# power_amp.net
KiCad netlist of a schematic drawn in Altium Designer
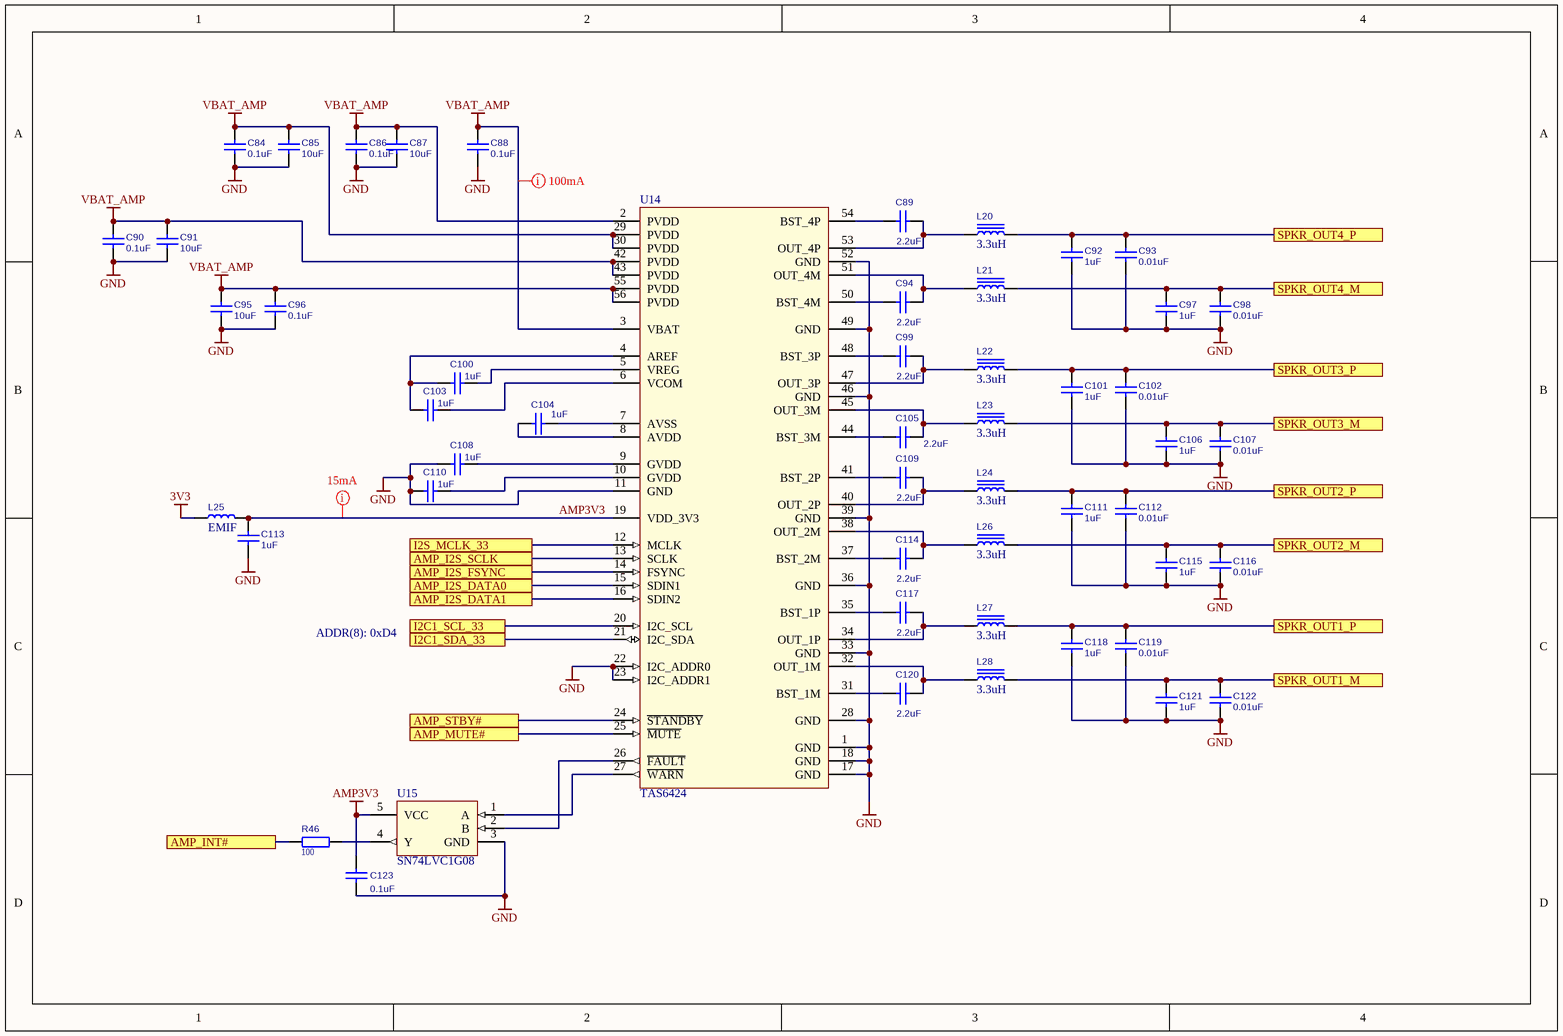
[diagram p0: power_amp.SchDoc]

(export (version "E")
  (design (tool "Eeschema 10.0.6"))
  (components
    (comp (ref "C84")
      (value "0.1uF")
      (footprint "Capacitors:C0603")
      (description "CAP_NPOL")
      (fields (field (name "Comment") "C1608X7R1H104K080AA"))
      (libsource (lib "capacitors") (part "CAP_NPOL"))
    )
    (comp (ref "C85")
      (value "10uF")
      (footprint "Capacitors:C0805")
      (description "CAP_NPOL")
      (fields (field (name "Comment") "GRM21BR61E106KA73L"))
      (libsource (lib "capacitors") (part "CAP_NPOL"))
    )
    (comp (ref "C86")
      (value "0.1uF")
      (footprint "Capacitors:C0603")
      (description "CAP_NPOL")
      (fields (field (name "Comment") "C1608X7R1H104K080AA"))
      (libsource (lib "capacitors") (part "CAP_NPOL"))
    )
    (comp (ref "C87")
      (value "10uF")
      (footprint "Capacitors:C0805")
      (description "CAP_NPOL")
      (fields (field (name "Comment") "GRM21BR61E106KA73L"))
      (libsource (lib "capacitors") (part "CAP_NPOL"))
    )
    (comp (ref "C88")
      (value "0.1uF")
      (footprint "Capacitors:C0603")
      (description "CAP_NPOL")
      (fields (field (name "Comment") "C1608X7R1H104K080AA"))
      (libsource (lib "capacitors") (part "CAP_NPOL"))
    )
    (comp (ref "C89")
      (value "2.2uF")
      (footprint "Capacitors:C0603")
      (description "CAP_NPOL")
      (fields (field (name "Comment") "GRM188R61H225KE11D"))
      (libsource (lib "capacitors") (part "CAP_NPOL"))
    )
    (comp (ref "C90")
      (value "0.1uF")
      (footprint "Capacitors:C0603")
      (description "CAP_NPOL")
      (fields (field (name "Comment") "C1608X7R1H104K080AA"))
      (libsource (lib "capacitors") (part "CAP_NPOL"))
    )
    (comp (ref "C91")
      (value "10uF")
      (footprint "Capacitors:C0805")
      (description "CAP_NPOL")
      (fields (field (name "Comment") "GRM21BR61E106KA73L"))
      (libsource (lib "capacitors") (part "CAP_NPOL"))
    )
    (comp (ref "C92")
      (value "1uF")
      (footprint "Capacitors:C0603")
      (description "CAP_NPOL")
      (fields (field (name "Comment") "CC0603KRX7R9BB105"))
      (libsource (lib "capacitors") (part "CAP_NPOL"))
    )
    (comp (ref "C93")
      (value "0.01uF")
      (footprint "Capacitors:C0603")
      (description "CAP_NPOL")
      (fields (field (name "Comment") "CL10B103KB8NNNC"))
      (libsource (lib "capacitors") (part "CAP_NPOL"))
    )
    (comp (ref "C94")
      (value "2.2uF")
      (footprint "Capacitors:C0603")
      (description "CAP_NPOL")
      (fields (field (name "Comment") "GRM188R61H225KE11D"))
      (libsource (lib "capacitors") (part "CAP_NPOL"))
    )
    (comp (ref "C95")
      (value "10uF")
      (footprint "Capacitors:C0805")
      (description "CAP_NPOL")
      (fields (field (name "Comment") "GRM21BR61E106KA73L"))
      (libsource (lib "capacitors") (part "CAP_NPOL"))
    )
    (comp (ref "C96")
      (value "0.1uF")
      (footprint "Capacitors:C0603")
      (description "CAP_NPOL")
      (fields (field (name "Comment") "C1608X7R1H104K080AA"))
      (libsource (lib "capacitors") (part "CAP_NPOL"))
    )
    (comp (ref "C97")
      (value "1uF")
      (footprint "Capacitors:C0603")
      (description "CAP_NPOL")
      (fields (field (name "Comment") "CC0603KRX7R9BB105"))
      (libsource (lib "capacitors") (part "CAP_NPOL"))
    )
    (comp (ref "C98")
      (value "0.01uF")
      (footprint "Capacitors:C0603")
      (description "CAP_NPOL")
      (fields (field (name "Comment") "CL10B103KB8NNNC"))
      (libsource (lib "capacitors") (part "CAP_NPOL"))
    )
    (comp (ref "C99")
      (value "2.2uF")
      (footprint "Capacitors:C0603")
      (description "CAP_NPOL")
      (fields (field (name "Comment") "GRM188R61H225KE11D"))
      (libsource (lib "capacitors") (part "CAP_NPOL"))
    )
    (comp (ref "C100")
      (value "1uF")
      (footprint "Capacitors:C0603")
      (description "CAP_NPOL")
      (fields (field (name "Comment") "CC0603KRX7R9BB105"))
      (libsource (lib "capacitors") (part "CAP_NPOL"))
    )
    (comp (ref "C101")
      (value "1uF")
      (footprint "Capacitors:C0603")
      (description "CAP_NPOL")
      (fields (field (name "Comment") "CC0603KRX7R9BB105"))
      (libsource (lib "capacitors") (part "CAP_NPOL"))
    )
    (comp (ref "C102")
      (value "0.01uF")
      (footprint "Capacitors:C0603")
      (description "CAP_NPOL")
      (fields (field (name "Comment") "CL10B103KB8NNNC"))
      (libsource (lib "capacitors") (part "CAP_NPOL"))
    )
    (comp (ref "C103")
      (value "1uF")
      (footprint "Capacitors:C0603")
      (description "CAP_NPOL")
      (fields (field (name "Comment") "CC0603KRX7R9BB105"))
      (libsource (lib "capacitors") (part "CAP_NPOL"))
    )
    (comp (ref "C104")
      (value "1uF")
      (footprint "Capacitors:C0603")
      (description "CAP_NPOL")
      (fields (field (name "Comment") "CC0603KRX7R9BB105"))
      (libsource (lib "capacitors") (part "CAP_NPOL"))
    )
    (comp (ref "C105")
      (value "2.2uF")
      (footprint "Capacitors:C0603")
      (description "CAP_NPOL")
      (fields (field (name "Comment") "GRM188R61H225KE11D"))
      (libsource (lib "capacitors") (part "CAP_NPOL"))
    )
    (comp (ref "C106")
      (value "1uF")
      (footprint "Capacitors:C0603")
      (description "CAP_NPOL")
      (fields (field (name "Comment") "CC0603KRX7R9BB105"))
      (libsource (lib "capacitors") (part "CAP_NPOL"))
    )
    (comp (ref "C107")
      (value "0.01uF")
      (footprint "Capacitors:C0603")
      (description "CAP_NPOL")
      (fields (field (name "Comment") "CL10B103KB8NNNC"))
      (libsource (lib "capacitors") (part "CAP_NPOL"))
    )
    (comp (ref "C108")
      (value "1uF")
      (footprint "Capacitors:C0603")
      (description "CAP_NPOL")
      (fields (field (name "Comment") "CC0603KRX7R9BB105"))
      (libsource (lib "capacitors") (part "CAP_NPOL"))
    )
    (comp (ref "C109")
      (value "2.2uF")
      (footprint "Capacitors:C0603")
      (description "CAP_NPOL")
      (fields (field (name "Comment") "GRM188R61H225KE11D"))
      (libsource (lib "capacitors") (part "CAP_NPOL"))
    )
    (comp (ref "C110")
      (value "1uF")
      (footprint "Capacitors:C0603")
      (description "CAP_NPOL")
      (fields (field (name "Comment") "CC0603KRX7R9BB105"))
      (libsource (lib "capacitors") (part "CAP_NPOL"))
    )
    (comp (ref "C111")
      (value "1uF")
      (footprint "Capacitors:C0603")
      (description "CAP_NPOL")
      (fields (field (name "Comment") "CC0603KRX7R9BB105"))
      (libsource (lib "capacitors") (part "CAP_NPOL"))
    )
    (comp (ref "C112")
      (value "0.01uF")
      (footprint "Capacitors:C0603")
      (description "CAP_NPOL")
      (fields (field (name "Comment") "CL10B103KB8NNNC"))
      (libsource (lib "capacitors") (part "CAP_NPOL"))
    )
    (comp (ref "C113")
      (value "1uF")
      (footprint "Capacitors:C0603")
      (description "CAP_NPOL")
      (fields (field (name "Comment") "CC0603KRX7R9BB105"))
      (libsource (lib "capacitors") (part "CAP_NPOL"))
    )
    (comp (ref "C114")
      (value "2.2uF")
      (footprint "Capacitors:C0603")
      (description "CAP_NPOL")
      (fields (field (name "Comment") "GRM188R61H225KE11D"))
      (libsource (lib "capacitors") (part "CAP_NPOL"))
    )
    (comp (ref "C115")
      (value "1uF")
      (footprint "Capacitors:C0603")
      (description "CAP_NPOL")
      (fields (field (name "Comment") "CC0603KRX7R9BB105"))
      (libsource (lib "capacitors") (part "CAP_NPOL"))
    )
    (comp (ref "C116")
      (value "0.01uF")
      (footprint "Capacitors:C0603")
      (description "CAP_NPOL")
      (fields (field (name "Comment") "CL10B103KB8NNNC"))
      (libsource (lib "capacitors") (part "CAP_NPOL"))
    )
    (comp (ref "C117")
      (value "2.2uF")
      (footprint "Capacitors:C0603")
      (description "CAP_NPOL")
      (fields (field (name "Comment") "GRM188R61H225KE11D"))
      (libsource (lib "capacitors") (part "CAP_NPOL"))
    )
    (comp (ref "C118")
      (value "1uF")
      (footprint "Capacitors:C0603")
      (description "CAP_NPOL")
      (fields (field (name "Comment") "CC0603KRX7R9BB105"))
      (libsource (lib "capacitors") (part "CAP_NPOL"))
    )
    (comp (ref "C119")
      (value "0.01uF")
      (footprint "Capacitors:C0603")
      (description "CAP_NPOL")
      (fields (field (name "Comment") "CL10B103KB8NNNC"))
      (libsource (lib "capacitors") (part "CAP_NPOL"))
    )
    (comp (ref "C120")
      (value "2.2uF")
      (footprint "Capacitors:C0603")
      (description "CAP_NPOL")
      (fields (field (name "Comment") "GRM188R61H225KE11D"))
      (libsource (lib "capacitors") (part "CAP_NPOL"))
    )
    (comp (ref "C121")
      (value "1uF")
      (footprint "Capacitors:C0603")
      (description "CAP_NPOL")
      (fields (field (name "Comment") "CC0603KRX7R9BB105"))
      (libsource (lib "capacitors") (part "CAP_NPOL"))
    )
    (comp (ref "C122")
      (value "0.01uF")
      (footprint "Capacitors:C0603")
      (description "CAP_NPOL")
      (fields (field (name "Comment") "CL10B103KB8NNNC"))
      (libsource (lib "capacitors") (part "CAP_NPOL"))
    )
    (comp (ref "C123")
      (value "0.1uF")
      (footprint "Capacitors:C0603")
      (description "CAP_NPOL")
      (fields (field (name "Comment") "CC0603KRX7R9BB104"))
      (libsource (lib "capacitors") (part "CAP_NPOL"))
    )
    (comp (ref "L20")
      (value "3.3uH")
      (footprint "IHLP-2525CZ")
      (description "IND_W_IRON")
      (fields (field (name "Comment") "IHLP2525CZER3R3M01"))
      (libsource (lib "inductors") (part "IND_W_IRON"))
    )
    (comp (ref "L21")
      (value "3.3uH")
      (footprint "IHLP-2525CZ")
      (description "IND_W_IRON")
      (fields (field (name "Comment") "IHLP2525CZER3R3M01"))
      (libsource (lib "inductors") (part "IND_W_IRON"))
    )
    (comp (ref "L22")
      (value "3.3uH")
      (footprint "IHLP-2525CZ")
      (description "IND_W_IRON")
      (fields (field (name "Comment") "IHLP2525CZER3R3M01"))
      (libsource (lib "inductors") (part "IND_W_IRON"))
    )
    (comp (ref "L23")
      (value "3.3uH")
      (footprint "IHLP-2525CZ")
      (description "IND_W_IRON")
      (fields (field (name "Comment") "IHLP2525CZER3R3M01"))
      (libsource (lib "inductors") (part "IND_W_IRON"))
    )
    (comp (ref "L24")
      (value "3.3uH")
      (footprint "IHLP-2525CZ")
      (description "IND_W_IRON")
      (fields (field (name "Comment") "IHLP2525CZER3R3M01"))
      (libsource (lib "inductors") (part "IND_W_IRON"))
    )
    (comp (ref "L25")
      (value "EMIF")
      (footprint "IND0805")
      (description "IND_WO_IRON")
      (fields (field (name "Comment") "BLM21PG221SN1D"))
      (libsource (lib "inductors") (part "IND_WO_IRON"))
    )
    (comp (ref "L26")
      (value "3.3uH")
      (footprint "IHLP-2525CZ")
      (description "IND_W_IRON")
      (fields (field (name "Comment") "IHLP2525CZER3R3M01"))
      (libsource (lib "inductors") (part "IND_W_IRON"))
    )
    (comp (ref "L27")
      (value "3.3uH")
      (footprint "IHLP-2525CZ")
      (description "IND_W_IRON")
      (fields (field (name "Comment") "IHLP2525CZER3R3M01"))
      (libsource (lib "inductors") (part "IND_W_IRON"))
    )
    (comp (ref "L28")
      (value "3.3uH")
      (footprint "IHLP-2525CZ")
      (description "IND_W_IRON")
      (fields (field (name "Comment") "IHLP2525CZER3R3M01"))
      (libsource (lib "inductors") (part "IND_W_IRON"))
    )
    (comp (ref "R46")
      (value "100")
      (footprint "R0603")
      (description "RES")
      (libsource (lib "resistors") (part "RESISTOR"))
    )
    (comp (ref "U14") (value "TAS6424") (footprint "HSSOP-56") (libsource (lib "TAS6424") (part "TAS6424")))
    (comp (ref "U15")
      (value "SN74LVC1G08")
      (footprint "SOT-23-5")
      (fields (field (name "Comment") "SN74LVC1G08DBVR"))
      (libsource (lib "SN74LVC1G08") (part "SN74LVC1G08"))
    )
  )
  (nets
    (net (code "1") (name "/AMP_I2S_DATA0") (class "Default")
      (node (ref "U14") (pin "15") (pinfunction "SDIN1_15") (pintype "input"))
    )
    (net (code "2") (name "/AMP_I2S_DATA1") (class "Default")
      (node (ref "U14") (pin "16") (pinfunction "SDIN2_16") (pintype "input"))
    )
    (net (code "3") (name "/AMP_I2S_FSYNC") (class "Default")
      (node (ref "U14") (pin "14") (pinfunction "FSYNC_14") (pintype "input"))
    )
    (net (code "4") (name "/AMP_I2S_SCLK") (class "Default")
      (node (ref "U14") (pin "13") (pinfunction "SCLK_13") (pintype "input"))
    )
    (net (code "5") (name "/AMP_INT#") (class "Default")
      (node (ref "R46") (pin "1") (pinfunction "1_1") (pintype "passive"))
    )
    (net (code "6") (name "/AMP_MUTE#") (class "Default")
      (node (ref "U14") (pin "25") (pinfunction "~{MUTE}_25") (pintype "input"))
    )
    (net (code "7") (name "/AMP_STBY#") (class "Default")
      (node (ref "U14") (pin "24") (pinfunction "~{STANDBY}_24") (pintype "input"))
    )
    (net (code "8") (name "/I2C1_SCL_33") (class "Default")
      (node (ref "U14") (pin "20") (pinfunction "I2C_SCL_20") (pintype "input"))
    )
    (net (code "9") (name "/I2C1_SDA_33") (class "Default")
      (node (ref "U14") (pin "21") (pinfunction "I2C_SDA_21") (pintype "bidirectional"))
    )
    (net (code "10") (name "/I2S_MCLK_33") (class "Default")
      (node (ref "U14") (pin "12") (pinfunction "MCLK_12") (pintype "input"))
    )
    (net (code "11") (name "/SPKR_OUT1_M") (class "Default")
      (node (ref "C121") (pin "1") (pinfunction "1_1") (pintype "passive"))
      (node (ref "C122") (pin "1") (pinfunction "1_1") (pintype "passive"))
      (node (ref "L28") (pin "2") (pintype "passive"))
    )
    (net (code "12") (name "/SPKR_OUT1_P") (class "Default")
      (node (ref "C118") (pin "1") (pinfunction "1_1") (pintype "passive"))
      (node (ref "C119") (pin "1") (pinfunction "1_1") (pintype "passive"))
      (node (ref "L27") (pin "2") (pintype "passive"))
    )
    (net (code "13") (name "/SPKR_OUT2_M") (class "Default")
      (node (ref "C115") (pin "1") (pinfunction "1_1") (pintype "passive"))
      (node (ref "C116") (pin "1") (pinfunction "1_1") (pintype "passive"))
      (node (ref "L26") (pin "2") (pintype "passive"))
    )
    (net (code "14") (name "/SPKR_OUT2_P") (class "Default")
      (node (ref "C111") (pin "1") (pinfunction "1_1") (pintype "passive"))
      (node (ref "C112") (pin "1") (pinfunction "1_1") (pintype "passive"))
      (node (ref "L24") (pin "2") (pintype "passive"))
    )
    (net (code "15") (name "/SPKR_OUT3_M") (class "Default")
      (node (ref "C106") (pin "1") (pinfunction "1_1") (pintype "passive"))
      (node (ref "C107") (pin "1") (pinfunction "1_1") (pintype "passive"))
      (node (ref "L23") (pin "2") (pintype "passive"))
    )
    (net (code "16") (name "/SPKR_OUT3_P") (class "Default")
      (node (ref "C101") (pin "1") (pinfunction "1_1") (pintype "passive"))
      (node (ref "C102") (pin "1") (pinfunction "1_1") (pintype "passive"))
      (node (ref "L22") (pin "2") (pintype "passive"))
    )
    (net (code "17") (name "/SPKR_OUT4_M") (class "Default")
      (node (ref "C97") (pin "1") (pinfunction "1_1") (pintype "passive"))
      (node (ref "C98") (pin "1") (pinfunction "1_1") (pintype "passive"))
      (node (ref "L21") (pin "2") (pintype "passive"))
    )
    (net (code "18") (name "/SPKR_OUT4_P") (class "Default")
      (node (ref "C92") (pin "1") (pinfunction "1_1") (pintype "passive"))
      (node (ref "C93") (pin "1") (pinfunction "1_1") (pintype "passive"))
      (node (ref "L20") (pin "2") (pintype "passive"))
    )
    (net (code "19") (name "3V3") (class "Default") (node (ref "L25") (pin "2") (pintype "passive")))
    (net (code "20") (name "AMP3V3") (class "Default")
      (node (ref "C113") (pin "1") (pinfunction "1_1") (pintype "passive"))
      (node (ref "C123") (pin "1") (pinfunction "1_1") (pintype "passive"))
      (node (ref "L25") (pin "1") (pintype "passive"))
      (node (ref "U14") (pin "19") (pinfunction "VDD_3V3_19") (pintype "power_in"))
      (node (ref "U15") (pin "5") (pinfunction "VCC_5") (pintype "power_in"))
    )
    (net (code "21") (name "GND") (class "Default")
      (node (ref "C101") (pin "2") (pinfunction "2_2") (pintype "passive"))
      (node (ref "C102") (pin "2") (pinfunction "2_2") (pintype "passive"))
      (node (ref "C106") (pin "2") (pinfunction "2_2") (pintype "passive"))
      (node (ref "C107") (pin "2") (pinfunction "2_2") (pintype "passive"))
      (node (ref "C108") (pin "1") (pinfunction "1_1") (pintype "passive"))
      (node (ref "C110") (pin "1") (pinfunction "1_1") (pintype "passive"))
      (node (ref "C111") (pin "2") (pinfunction "2_2") (pintype "passive"))
      (node (ref "C112") (pin "2") (pinfunction "2_2") (pintype "passive"))
      (node (ref "C113") (pin "2") (pinfunction "2_2") (pintype "passive"))
      (node (ref "C115") (pin "2") (pinfunction "2_2") (pintype "passive"))
      (node (ref "C116") (pin "2") (pinfunction "2_2") (pintype "passive"))
      (node (ref "C118") (pin "2") (pinfunction "2_2") (pintype "passive"))
      (node (ref "C119") (pin "2") (pinfunction "2_2") (pintype "passive"))
      (node (ref "C121") (pin "2") (pinfunction "2_2") (pintype "passive"))
      (node (ref "C122") (pin "2") (pinfunction "2_2") (pintype "passive"))
      (node (ref "C123") (pin "2") (pinfunction "2_2") (pintype "passive"))
      (node (ref "C84") (pin "2") (pinfunction "2_2") (pintype "passive"))
      (node (ref "C85") (pin "2") (pinfunction "2_2") (pintype "passive"))
      (node (ref "C86") (pin "2") (pinfunction "2_2") (pintype "passive"))
      (node (ref "C87") (pin "2") (pinfunction "2_2") (pintype "passive"))
      (node (ref "C88") (pin "2") (pinfunction "2_2") (pintype "passive"))
      (node (ref "C90") (pin "2") (pinfunction "2_2") (pintype "passive"))
      (node (ref "C91") (pin "2") (pinfunction "2_2") (pintype "passive"))
      (node (ref "C92") (pin "2") (pinfunction "2_2") (pintype "passive"))
      (node (ref "C93") (pin "2") (pinfunction "2_2") (pintype "passive"))
      (node (ref "C95") (pin "2") (pinfunction "2_2") (pintype "passive"))
      (node (ref "C96") (pin "2") (pinfunction "2_2") (pintype "passive"))
      (node (ref "C97") (pin "2") (pinfunction "2_2") (pintype "passive"))
      (node (ref "C98") (pin "2") (pinfunction "2_2") (pintype "passive"))
      (node (ref "U14") (pin "1") (pinfunction "GND_1") (pintype "power_in"))
      (node (ref "U14") (pin "11") (pinfunction "GND_11") (pintype "power_in"))
      (node (ref "U14") (pin "17") (pinfunction "GND_17") (pintype "power_in"))
      (node (ref "U14") (pin "18") (pinfunction "GND_18") (pintype "power_in"))
      (node (ref "U14") (pin "22") (pinfunction "I2C_ADDR0_22") (pintype "input"))
      (node (ref "U14") (pin "23") (pinfunction "I2C_ADDR1_23") (pintype "input"))
      (node (ref "U14") (pin "28") (pinfunction "GND_28") (pintype "power_in"))
      (node (ref "U14") (pin "33") (pinfunction "GND_33") (pintype "power_in"))
      (node (ref "U14") (pin "36") (pinfunction "GND_36") (pintype "power_in"))
      (node (ref "U14") (pin "39") (pinfunction "GND_39") (pintype "power_in"))
      (node (ref "U14") (pin "46") (pinfunction "GND_46") (pintype "power_in"))
      (node (ref "U14") (pin "49") (pinfunction "GND_49") (pintype "power_in"))
      (node (ref "U14") (pin "52") (pinfunction "GND_52") (pintype "power_in"))
      (node (ref "U15") (pin "3") (pinfunction "GND_3") (pintype "power_in"))
    )
    (net (code "22") (name "Net-(C108-Pad2)") (class "Default")
      (node (ref "C108") (pin "2") (pinfunction "2_2") (pintype "passive"))
      (node (ref "U14") (pin "9") (pinfunction "GVDD_9") (pintype "power_in"))
    )
    (net (code "23") (name "Net-(C110-Pad2)") (class "Default")
      (node (ref "C110") (pin "2") (pinfunction "2_2") (pintype "passive"))
      (node (ref "U14") (pin "10") (pinfunction "GVDD_10") (pintype "power_in"))
    )
    (net (code "24") (name "Net-(U14-AREF)") (class "Default")
      (node (ref "C100") (pin "1") (pinfunction "1_1") (pintype "passive"))
      (node (ref "C103") (pin "1") (pinfunction "1_1") (pintype "passive"))
      (node (ref "U14") (pin "4") (pinfunction "AREF_4") (pintype "power_in"))
    )
    (net (code "25") (name "Net-(U14-AVDD)") (class "Default")
      (node (ref "C104") (pin "1") (pinfunction "1_1") (pintype "passive"))
      (node (ref "U14") (pin "8") (pinfunction "AVDD_8") (pintype "power_in"))
    )
    (net (code "26") (name "Net-(U14-AVSS)") (class "Default")
      (node (ref "C104") (pin "2") (pinfunction "2_2") (pintype "passive"))
      (node (ref "U14") (pin "7") (pinfunction "AVSS_7") (pintype "power_in"))
    )
    (net (code "27") (name "Net-(U14-BST_1M)") (class "Default")
      (node (ref "C120") (pin "2") (pinfunction "2_2") (pintype "passive"))
      (node (ref "U14") (pin "31") (pinfunction "BST_1M_31") (pintype "power_in"))
    )
    (net (code "28") (name "Net-(U14-BST_1P)") (class "Default")
      (node (ref "C117") (pin "2") (pinfunction "2_2") (pintype "passive"))
      (node (ref "U14") (pin "35") (pinfunction "BST_1P_35") (pintype "power_in"))
    )
    (net (code "29") (name "Net-(U14-BST_2M)") (class "Default")
      (node (ref "C114") (pin "2") (pinfunction "2_2") (pintype "passive"))
      (node (ref "U14") (pin "37") (pinfunction "BST_2M_37") (pintype "power_in"))
    )
    (net (code "30") (name "Net-(U14-BST_2P)") (class "Default")
      (node (ref "C109") (pin "2") (pinfunction "2_2") (pintype "passive"))
      (node (ref "U14") (pin "41") (pinfunction "BST_2P_41") (pintype "power_in"))
    )
    (net (code "31") (name "Net-(U14-BST_3M)") (class "Default")
      (node (ref "C105") (pin "2") (pinfunction "2_2") (pintype "passive"))
      (node (ref "U14") (pin "44") (pinfunction "BST_3M_44") (pintype "power_in"))
    )
    (net (code "32") (name "Net-(U14-BST_3P)") (class "Default")
      (node (ref "C99") (pin "2") (pinfunction "2_2") (pintype "passive"))
      (node (ref "U14") (pin "48") (pinfunction "BST_3P_48") (pintype "power_in"))
    )
    (net (code "33") (name "Net-(U14-BST_4M)") (class "Default")
      (node (ref "C94") (pin "2") (pinfunction "2_2") (pintype "passive"))
      (node (ref "U14") (pin "50") (pinfunction "BST_4M_50") (pintype "power_in"))
    )
    (net (code "34") (name "Net-(U14-BST_4P)") (class "Default")
      (node (ref "C89") (pin "2") (pinfunction "2_2") (pintype "passive"))
      (node (ref "U14") (pin "54") (pinfunction "BST_4P_54") (pintype "power_in"))
    )
    (net (code "35") (name "Net-(U14-OUT_1M)") (class "Default")
      (node (ref "C120") (pin "1") (pinfunction "1_1") (pintype "passive"))
      (node (ref "L28") (pin "1") (pintype "passive"))
      (node (ref "U14") (pin "32") (pinfunction "OUT_1M_32") (pintype "passive"))
    )
    (net (code "36") (name "Net-(U14-OUT_1P)") (class "Default")
      (node (ref "C117") (pin "1") (pinfunction "1_1") (pintype "passive"))
      (node (ref "L27") (pin "1") (pintype "passive"))
      (node (ref "U14") (pin "34") (pinfunction "OUT_1P_34") (pintype "passive"))
    )
    (net (code "37") (name "Net-(U14-OUT_2M)") (class "Default")
      (node (ref "C114") (pin "1") (pinfunction "1_1") (pintype "passive"))
      (node (ref "L26") (pin "1") (pintype "passive"))
      (node (ref "U14") (pin "38") (pinfunction "OUT_2M_38") (pintype "passive"))
    )
    (net (code "38") (name "Net-(U14-OUT_2P)") (class "Default")
      (node (ref "C109") (pin "1") (pinfunction "1_1") (pintype "passive"))
      (node (ref "L24") (pin "1") (pintype "passive"))
      (node (ref "U14") (pin "40") (pinfunction "OUT_2P_40") (pintype "passive"))
    )
    (net (code "39") (name "Net-(U14-OUT_3M)") (class "Default")
      (node (ref "C105") (pin "1") (pinfunction "1_1") (pintype "passive"))
      (node (ref "L23") (pin "1") (pintype "passive"))
      (node (ref "U14") (pin "45") (pinfunction "OUT_3M_45") (pintype "passive"))
    )
    (net (code "40") (name "Net-(U14-OUT_3P)") (class "Default")
      (node (ref "C99") (pin "1") (pinfunction "1_1") (pintype "passive"))
      (node (ref "L22") (pin "1") (pintype "passive"))
      (node (ref "U14") (pin "47") (pinfunction "OUT_3P_47") (pintype "passive"))
    )
    (net (code "41") (name "Net-(U14-OUT_4M)") (class "Default")
      (node (ref "C94") (pin "1") (pinfunction "1_1") (pintype "passive"))
      (node (ref "L21") (pin "1") (pintype "passive"))
      (node (ref "U14") (pin "51") (pinfunction "OUT_4M_51") (pintype "passive"))
    )
    (net (code "42") (name "Net-(U14-OUT_4P)") (class "Default")
      (node (ref "C89") (pin "1") (pinfunction "1_1") (pintype "passive"))
      (node (ref "L20") (pin "1") (pintype "passive"))
      (node (ref "U14") (pin "53") (pinfunction "OUT_4P_53") (pintype "passive"))
    )
    (net (code "43") (name "Net-(U14-VCOM)") (class "Default")
      (node (ref "C103") (pin "2") (pinfunction "2_2") (pintype "passive"))
      (node (ref "U14") (pin "6") (pinfunction "VCOM_6") (pintype "power_in"))
    )
    (net (code "44") (name "Net-(U14-VREG)") (class "Default")
      (node (ref "C100") (pin "2") (pinfunction "2_2") (pintype "passive"))
      (node (ref "U14") (pin "5") (pinfunction "VREG_5") (pintype "power_in"))
    )
    (net (code "45") (name "Net-(U14-~{FAULT})") (class "Default")
      (node (ref "U14") (pin "26") (pinfunction "~{FAULT}_26") (pintype "output"))
      (node (ref "U15") (pin "2") (pinfunction "B_2") (pintype "input"))
    )
    (net (code "46") (name "Net-(U14-~{WARN})") (class "Default")
      (node (ref "U14") (pin "27") (pinfunction "~{WARN}_27") (pintype "output"))
      (node (ref "U15") (pin "1") (pinfunction "A_1") (pintype "input"))
    )
    (net (code "47") (name "Net-(U15-Y)") (class "Default")
      (node (ref "R46") (pin "2") (pinfunction "2_2") (pintype "passive"))
      (node (ref "U15") (pin "4") (pinfunction "Y_4") (pintype "output"))
    )
    (net (code "48") (name "VBAT_AMP") (class "Default")
      (node (ref "C84") (pin "1") (pinfunction "1_1") (pintype "passive"))
      (node (ref "C85") (pin "1") (pinfunction "1_1") (pintype "passive"))
      (node (ref "C86") (pin "1") (pinfunction "1_1") (pintype "passive"))
      (node (ref "C87") (pin "1") (pinfunction "1_1") (pintype "passive"))
      (node (ref "C88") (pin "1") (pinfunction "1_1") (pintype "passive"))
      (node (ref "C90") (pin "1") (pinfunction "1_1") (pintype "passive"))
      (node (ref "C91") (pin "1") (pinfunction "1_1") (pintype "passive"))
      (node (ref "C95") (pin "1") (pinfunction "1_1") (pintype "passive"))
      (node (ref "C96") (pin "1") (pinfunction "1_1") (pintype "passive"))
      (node (ref "U14") (pin "2") (pinfunction "PVDD_2") (pintype "power_in"))
      (node (ref "U14") (pin "29") (pinfunction "PVDD_29") (pintype "power_in"))
      (node (ref "U14") (pin "3") (pinfunction "VBAT_3") (pintype "power_in"))
      (node (ref "U14") (pin "30") (pinfunction "PVDD_30") (pintype "power_in"))
      (node (ref "U14") (pin "42") (pinfunction "PVDD_42") (pintype "power_in"))
      (node (ref "U14") (pin "43") (pinfunction "PVDD_43") (pintype "power_in"))
      (node (ref "U14") (pin "55") (pinfunction "PVDD_55") (pintype "power_in"))
      (node (ref "U14") (pin "56") (pinfunction "PVDD_56") (pintype "power_in"))
    )
  )
)
